# ESP_Encoder_Layout.net
KiCad netlist of a schematic drawn in Altium Designer
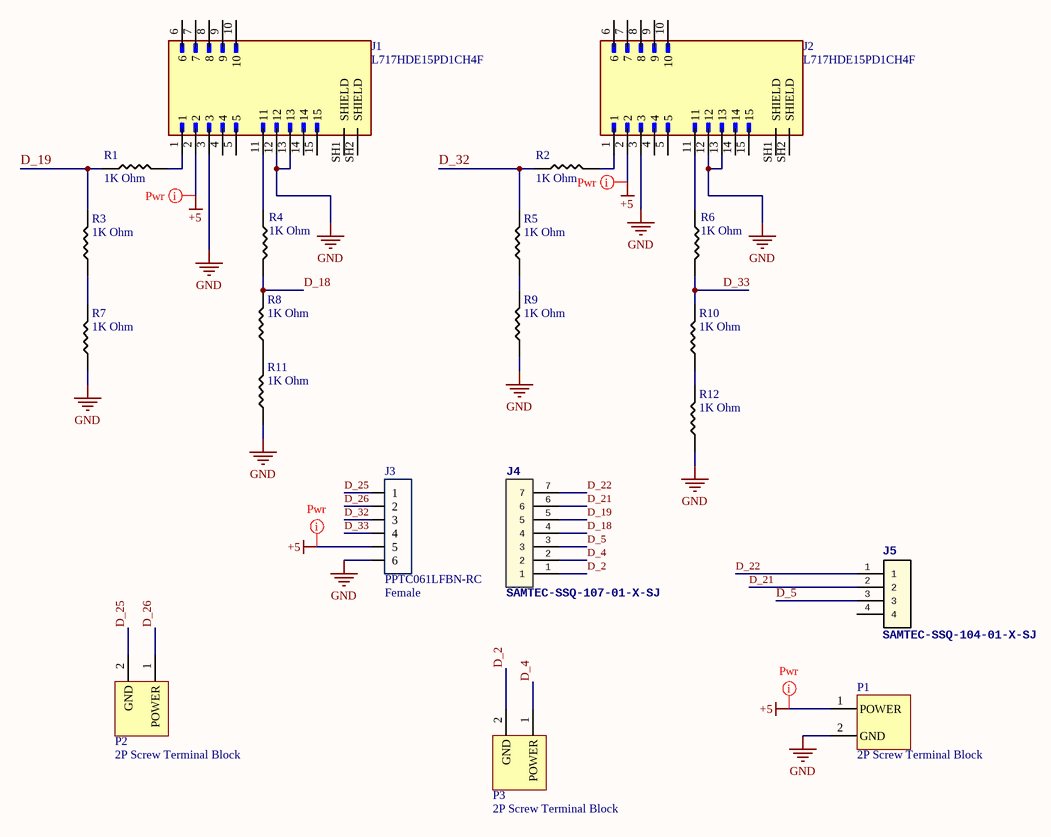
[diagram p0: ESP_Encoder Layout.SchDoc]

(export (version "E")
  (design (tool "Eeschema 10.0.6"))
  (components
    (comp (ref "J1")
      (value "L717HDE15PD1CH4F")
      (footprint "AMPHENOL_L717HDE15PD1CH4F")
      (fields (field (name "MF") "Amphenol ICC"))
      (libsource (lib "L717HDE15PD1CH4F") (part "L717HDE15PD1CH4F"))
    )
    (comp (ref "J2")
      (value "L717HDE15PD1CH4F")
      (footprint "AMPHENOL_L717HDE15PD1CH4F")
      (fields (field (name "MF") "Amphenol ICC"))
      (libsource (lib "L717HDE15PD1CH4F") (part "L717HDE15PD1CH4F"))
    )
    (comp (ref "J3")
      (value "PPTC061LFBN-RC")
      (footprint "6_PIN_100MIL -Female")
      (description "6 Position Header Connector 0.100\" (2.54mm) Through Hole Tin")
      (fields (field (name "LCSC PART#") "C40877") (field (name "ALTIUM_VALUE") "Female"))
      (libsource (lib "Capstone_Stock_Library") (part "JF_6_PIN_FEMALE"))
    )
    (comp (ref "J4")
      (value "SAMTEC-SSQ-107-01-X-SJ")
      (footprint "JF-7_SSQ-107-01-X-S")
      (description "2.54mm Brass Straight 1x7P 7 1 Straight,P=2.54mm  Female Headers ROHS")
      (fields (field (name "MFR PART #") "B-2200S07P-A120") (field (name "LCSC PART#") "C124418"))
      (libsource (lib "Capstone_Stock_Library") (part "JF_7_PIN_FEMALE"))
    )
    (comp (ref "J5")
      (value "SAMTEC-SSQ-104-01-X-SJ")
      (footprint "JF-4_SSQ-104-01-X-S")
      (fields (field (name "MFR PART #") "SSQ-104-01-X-SJ") (field (name "LCSC PART#") "C2718488"))
      (libsource (lib "Capstone_Stock_Library") (part "JF_4_PIN_FEMALE"))
    )
    (comp (ref "P1")
      (value "2P Screw Terminal Block")
      (footprint "P_Terminal block 3.5mm-pitch")
      (description "Green Straight pin 3.5mm  pitch; P=3.5mm  Screw terminal ROHS")
      (fields (field (name "MFR PART #") "KF350-3.5-2P") (field (name "MANUFACTURER") "Cixi Kefa Elec"))
      (libsource (lib "") (part "P_Terminal block_1"))
    )
    (comp (ref "P2")
      (value "2P Screw Terminal Block")
      (footprint "P_Terminal block 3.5mm-pitch")
      (description "Green Straight pin 3.5mm  pitch; P=3.5mm  Screw terminal ROHS")
      (fields (field (name "MFR PART #") "KF350-3.5-2P") (field (name "MANUFACTURER") "Cixi Kefa Elec"))
      (libsource (lib "Capstone_Stock_Library") (part "P_Terminal block"))
    )
    (comp (ref "P3")
      (value "2P Screw Terminal Block")
      (footprint "P_Terminal block 3.5mm-pitch")
      (description "Green Straight pin 3.5mm  pitch; P=3.5mm  Screw terminal ROHS")
      (fields (field (name "MFR PART #") "KF350-3.5-2P") (field (name "MANUFACTURER") "Cixi Kefa Elec"))
      (libsource (lib "Capstone_Stock_Library") (part "P_Terminal block"))
    )
    (comp (ref "R1")
      (value "1K Ohm")
      (footprint "1206_Passive_Resitor")
      (description "CHIP RESISTOR - SURFACE MOUNT 1KOHMS ±1% 1/4W 1206 ROHS")
      (fields (field (name "MFR PART #") "RNCP1206FTD1K00CT") (field (name "LCSC PART#") "C4410"))
      (libsource (lib "Capstone_Stock_Library") (part "R_1K_1206"))
    )
    (comp (ref "R2")
      (value "1K Ohm")
      (footprint "1206_Passive_Resitor")
      (description "CHIP RESISTOR - SURFACE MOUNT 1KOHMS ±1% 1/4W 1206 ROHS")
      (fields (field (name "MFR PART #") "RNCP1206FTD1K00CT") (field (name "LCSC PART#") "C4410"))
      (libsource (lib "Capstone_Stock_Library") (part "R_1K_1206"))
    )
    (comp (ref "R3")
      (value "1K Ohm")
      (footprint "1206_Passive_Resitor")
      (description "CHIP RESISTOR - SURFACE MOUNT 1KOHMS ±1% 1/4W 1206 ROHS")
      (fields (field (name "MFR PART #") "RNCP1206FTD1K00CT") (field (name "LCSC PART#") "C4410"))
      (libsource (lib "Capstone_Stock_Library") (part "R_1K_1206"))
    )
    (comp (ref "R4")
      (value "1K Ohm")
      (footprint "1206_Passive_Resitor")
      (description "CHIP RESISTOR - SURFACE MOUNT 1KOHMS ±1% 1/4W 1206 ROHS")
      (fields (field (name "MFR PART #") "RNCP1206FTD1K00CT") (field (name "LCSC PART#") "C4410"))
      (libsource (lib "Capstone_Stock_Library") (part "R_1K_1206"))
    )
    (comp (ref "R5")
      (value "1K Ohm")
      (footprint "1206_Passive_Resitor")
      (description "CHIP RESISTOR - SURFACE MOUNT 1KOHMS ±1% 1/4W 1206 ROHS")
      (fields (field (name "MFR PART #") "RNCP1206FTD1K00CT") (field (name "LCSC PART#") "C4410"))
      (libsource (lib "Capstone_Stock_Library") (part "R_1K_1206"))
    )
    (comp (ref "R6")
      (value "1K Ohm")
      (footprint "1206_Passive_Resitor")
      (description "CHIP RESISTOR - SURFACE MOUNT 1KOHMS ±1% 1/4W 1206 ROHS")
      (fields (field (name "MFR PART #") "RNCP1206FTD1K00CT") (field (name "LCSC PART#") "C4410"))
      (libsource (lib "Capstone_Stock_Library") (part "R_1K_1206"))
    )
    (comp (ref "R7")
      (value "1K Ohm")
      (footprint "1206_Passive_Resitor")
      (description "CHIP RESISTOR - SURFACE MOUNT 1KOHMS ±1% 1/4W 1206 ROHS")
      (fields (field (name "MFR PART #") "RNCP1206FTD1K00CT") (field (name "LCSC PART#") "C4410"))
      (libsource (lib "Capstone_Stock_Library") (part "R_1K_1206"))
    )
    (comp (ref "R8")
      (value "1K Ohm")
      (footprint "1206_Passive_Resitor")
      (description "CHIP RESISTOR - SURFACE MOUNT 1KOHMS ±1% 1/4W 1206 ROHS")
      (fields (field (name "MFR PART #") "RNCP1206FTD1K00CT") (field (name "LCSC PART#") "C4410"))
      (libsource (lib "Capstone_Stock_Library") (part "R_1K_1206"))
    )
    (comp (ref "R9")
      (value "1K Ohm")
      (footprint "1206_Passive_Resitor")
      (description "CHIP RESISTOR - SURFACE MOUNT 1KOHMS ±1% 1/4W 1206 ROHS")
      (fields (field (name "MFR PART #") "RNCP1206FTD1K00CT") (field (name "LCSC PART#") "C4410"))
      (libsource (lib "Capstone_Stock_Library") (part "R_1K_1206"))
    )
    (comp (ref "R10")
      (value "1K Ohm")
      (footprint "1206_Passive_Resitor")
      (description "CHIP RESISTOR - SURFACE MOUNT 1KOHMS ±1% 1/4W 1206 ROHS")
      (fields (field (name "MFR PART #") "RNCP1206FTD1K00CT") (field (name "LCSC PART#") "C4410"))
      (libsource (lib "Capstone_Stock_Library") (part "R_1K_1206"))
    )
    (comp (ref "R11")
      (value "1K Ohm")
      (footprint "1206_Passive_Resitor")
      (description "CHIP RESISTOR - SURFACE MOUNT 1KOHMS ±1% 1/4W 1206 ROHS")
      (fields (field (name "MFR PART #") "RNCP1206FTD1K00CT") (field (name "LCSC PART#") "C4410"))
      (libsource (lib "Capstone_Stock_Library") (part "R_1K_1206"))
    )
    (comp (ref "R12")
      (value "1K Ohm")
      (footprint "1206_Passive_Resitor")
      (description "CHIP RESISTOR - SURFACE MOUNT 1KOHMS ±1% 1/4W 1206 ROHS")
      (fields (field (name "MFR PART #") "RNCP1206FTD1K00CT") (field (name "LCSC PART#") "C4410"))
      (libsource (lib "Capstone_Stock_Library") (part "R_1K_1206"))
    )
  )
  (nets
    (net (code "1") (name "+5") (class "Default")
      (node (ref "J1") (pin "2") (pinfunction "2_2") (pintype "passive"))
      (node (ref "J2") (pin "2") (pinfunction "2_2") (pintype "passive"))
      (node (ref "J3") (pin "5") (pinfunction "5_5") (pintype "passive"))
      (node (ref "P1") (pin "1") (pinfunction "POWER_1") (pintype "passive"))
    )
    (net (code "2") (name "/D_2") (class "Default")
      (node (ref "J4") (pin "1") (pinfunction "1_1") (pintype "passive"))
      (node (ref "P3") (pin "2") (pinfunction "GND_2") (pintype "passive"))
    )
    (net (code "3") (name "/D_4") (class "Default")
      (node (ref "J4") (pin "2") (pinfunction "2_2") (pintype "passive"))
      (node (ref "P3") (pin "1") (pinfunction "POWER_1") (pintype "passive"))
    )
    (net (code "4") (name "/D_5") (class "Default")
      (node (ref "J4") (pin "3") (pinfunction "3_3") (pintype "passive"))
      (node (ref "J5") (pin "3") (pinfunction "3_3") (pintype "passive"))
    )
    (net (code "5") (name "/D_18") (class "Default")
      (node (ref "J4") (pin "4") (pinfunction "4_4") (pintype "passive"))
      (node (ref "R4") (pin "2") (pinfunction "2_2") (pintype "passive"))
      (node (ref "R8") (pin "2") (pinfunction "2_2") (pintype "passive"))
    )
    (net (code "6") (name "/D_19") (class "Default")
      (node (ref "J4") (pin "5") (pinfunction "5_5") (pintype "passive"))
      (node (ref "R1") (pin "1") (pinfunction "1_1") (pintype "passive"))
      (node (ref "R3") (pin "2") (pinfunction "2_2") (pintype "passive"))
    )
    (net (code "7") (name "/D_21") (class "Default")
      (node (ref "J4") (pin "6") (pinfunction "6_6") (pintype "passive"))
      (node (ref "J5") (pin "2") (pinfunction "2_2") (pintype "passive"))
    )
    (net (code "8") (name "/D_22") (class "Default")
      (node (ref "J4") (pin "7") (pinfunction "7_7") (pintype "passive"))
      (node (ref "J5") (pin "1") (pinfunction "1_1") (pintype "passive"))
    )
    (net (code "9") (name "/D_25") (class "Default")
      (node (ref "J3") (pin "1") (pinfunction "1_1") (pintype "passive"))
      (node (ref "P2") (pin "2") (pinfunction "GND_2") (pintype "passive"))
    )
    (net (code "10") (name "/D_26") (class "Default")
      (node (ref "J3") (pin "2") (pinfunction "2_2") (pintype "passive"))
      (node (ref "P2") (pin "1") (pinfunction "POWER_1") (pintype "passive"))
    )
    (net (code "11") (name "/D_32") (class "Default")
      (node (ref "J3") (pin "3") (pinfunction "3_3") (pintype "passive"))
      (node (ref "R2") (pin "1") (pinfunction "1_1") (pintype "passive"))
      (node (ref "R5") (pin "2") (pinfunction "2_2") (pintype "passive"))
    )
    (net (code "12") (name "/D_33") (class "Default")
      (node (ref "J3") (pin "4") (pinfunction "4_4") (pintype "passive"))
      (node (ref "R10") (pin "2") (pinfunction "2_2") (pintype "passive"))
      (node (ref "R6") (pin "2") (pinfunction "2_2") (pintype "passive"))
    )
    (net (code "13") (name "GND") (class "Default")
      (node (ref "J1") (pin "12") (pinfunction "12_12") (pintype "passive"))
      (node (ref "J1") (pin "13") (pinfunction "13_13") (pintype "passive"))
      (node (ref "J1") (pin "3") (pinfunction "3_3") (pintype "passive"))
      (node (ref "J2") (pin "12") (pinfunction "12_12") (pintype "passive"))
      (node (ref "J2") (pin "13") (pinfunction "13_13") (pintype "passive"))
      (node (ref "J2") (pin "3") (pinfunction "3_3") (pintype "passive"))
      (node (ref "J3") (pin "6") (pinfunction "6_6") (pintype "passive"))
      (node (ref "P1") (pin "2") (pinfunction "GND_2") (pintype "passive"))
      (node (ref "R11") (pin "1") (pinfunction "1_1") (pintype "passive"))
      (node (ref "R12") (pin "1") (pinfunction "1_1") (pintype "passive"))
      (node (ref "R7") (pin "1") (pinfunction "1_1") (pintype "passive"))
      (node (ref "R9") (pin "1") (pinfunction "1_1") (pintype "passive"))
    )
    (net (code "14") (name "Net-(J1-Pad1)") (class "Default")
      (node (ref "J1") (pin "1") (pinfunction "1_1") (pintype "passive"))
      (node (ref "R1") (pin "2") (pinfunction "2_2") (pintype "passive"))
    )
    (net (code "15") (name "Net-(J1-Pad11)") (class "Default")
      (node (ref "J1") (pin "11") (pinfunction "11_11") (pintype "passive"))
      (node (ref "R4") (pin "1") (pinfunction "1_1") (pintype "passive"))
    )
    (net (code "16") (name "Net-(J2-Pad1)") (class "Default")
      (node (ref "J2") (pin "1") (pinfunction "1_1") (pintype "passive"))
      (node (ref "R2") (pin "2") (pinfunction "2_2") (pintype "passive"))
    )
    (net (code "17") (name "Net-(J2-Pad11)") (class "Default")
      (node (ref "J2") (pin "11") (pinfunction "11_11") (pintype "passive"))
      (node (ref "R6") (pin "1") (pinfunction "1_1") (pintype "passive"))
    )
    (net (code "18") (name "Net-(R3-Pad1)") (class "Default")
      (node (ref "R3") (pin "1") (pinfunction "1_1") (pintype "passive"))
      (node (ref "R7") (pin "2") (pinfunction "2_2") (pintype "passive"))
    )
    (net (code "19") (name "Net-(R5-Pad1)") (class "Default")
      (node (ref "R5") (pin "1") (pinfunction "1_1") (pintype "passive"))
      (node (ref "R9") (pin "2") (pinfunction "2_2") (pintype "passive"))
    )
    (net (code "20") (name "Net-(R10-Pad1)") (class "Default")
      (node (ref "R10") (pin "1") (pinfunction "1_1") (pintype "passive"))
      (node (ref "R12") (pin "2") (pinfunction "2_2") (pintype "passive"))
    )
    (net (code "21") (name "Net-(R11-Pad2)") (class "Default")
      (node (ref "R11") (pin "2") (pinfunction "2_2") (pintype "passive"))
      (node (ref "R8") (pin "1") (pinfunction "1_1") (pintype "passive"))
    )
    (net (code "22") (name "unconnected-(J1-Pad4)") (class "Default")
      (node (ref "J1") (pin "4") (pinfunction "4_4") (pintype "passive"))
    )
    (net (code "23") (name "unconnected-(J1-Pad5)") (class "Default")
      (node (ref "J1") (pin "5") (pinfunction "5_5") (pintype "passive"))
    )
    (net (code "24") (name "unconnected-(J1-Pad6)") (class "Default")
      (node (ref "J1") (pin "6") (pinfunction "6_6") (pintype "passive"))
    )
    (net (code "25") (name "unconnected-(J1-Pad7)") (class "Default")
      (node (ref "J1") (pin "7") (pinfunction "7_7") (pintype "passive"))
    )
    (net (code "26") (name "unconnected-(J1-Pad8)") (class "Default")
      (node (ref "J1") (pin "8") (pinfunction "8_8") (pintype "passive"))
    )
    (net (code "27") (name "unconnected-(J1-Pad9)") (class "Default")
      (node (ref "J1") (pin "9") (pinfunction "9_9") (pintype "passive"))
    )
    (net (code "28") (name "unconnected-(J1-Pad10)") (class "Default")
      (node (ref "J1") (pin "10") (pinfunction "10_10") (pintype "passive"))
    )
    (net (code "29") (name "unconnected-(J1-Pad14)") (class "Default")
      (node (ref "J1") (pin "14") (pinfunction "14_14") (pintype "passive"))
    )
    (net (code "30") (name "unconnected-(J1-Pad15)") (class "Default")
      (node (ref "J1") (pin "15") (pinfunction "15_15") (pintype "passive"))
    )
    (net (code "31") (name "unconnected-(J1-SHIELD-PadSH1)") (class "Default")
      (node (ref "J1") (pin "SH1") (pinfunction "SHIELD_SH1") (pintype "passive"))
    )
    (net (code "32") (name "unconnected-(J1-SHIELD-PadSH2)") (class "Default")
      (node (ref "J1") (pin "SH2") (pinfunction "SHIELD_SH2") (pintype "passive"))
    )
    (net (code "33") (name "unconnected-(J2-Pad4)") (class "Default")
      (node (ref "J2") (pin "4") (pinfunction "4_4") (pintype "passive"))
    )
    (net (code "34") (name "unconnected-(J2-Pad5)") (class "Default")
      (node (ref "J2") (pin "5") (pinfunction "5_5") (pintype "passive"))
    )
    (net (code "35") (name "unconnected-(J2-Pad6)") (class "Default")
      (node (ref "J2") (pin "6") (pinfunction "6_6") (pintype "passive"))
    )
    (net (code "36") (name "unconnected-(J2-Pad7)") (class "Default")
      (node (ref "J2") (pin "7") (pinfunction "7_7") (pintype "passive"))
    )
    (net (code "37") (name "unconnected-(J2-Pad8)") (class "Default")
      (node (ref "J2") (pin "8") (pinfunction "8_8") (pintype "passive"))
    )
    (net (code "38") (name "unconnected-(J2-Pad9)") (class "Default")
      (node (ref "J2") (pin "9") (pinfunction "9_9") (pintype "passive"))
    )
    (net (code "39") (name "unconnected-(J2-Pad10)") (class "Default")
      (node (ref "J2") (pin "10") (pinfunction "10_10") (pintype "passive"))
    )
    (net (code "40") (name "unconnected-(J2-Pad14)") (class "Default")
      (node (ref "J2") (pin "14") (pinfunction "14_14") (pintype "passive"))
    )
    (net (code "41") (name "unconnected-(J2-Pad15)") (class "Default")
      (node (ref "J2") (pin "15") (pinfunction "15_15") (pintype "passive"))
    )
    (net (code "42") (name "unconnected-(J2-SHIELD-PadSH1)") (class "Default")
      (node (ref "J2") (pin "SH1") (pinfunction "SHIELD_SH1") (pintype "passive"))
    )
    (net (code "43") (name "unconnected-(J2-SHIELD-PadSH2)") (class "Default")
      (node (ref "J2") (pin "SH2") (pinfunction "SHIELD_SH2") (pintype "passive"))
    )
    (net (code "44") (name "unconnected-(J5-Pad4)") (class "Default")
      (node (ref "J5") (pin "4") (pinfunction "4_4") (pintype "passive"))
    )
  )
)
